# Tiny_BLE_V1_0.net
KiCad netlist of a schematic drawn in EAGLE
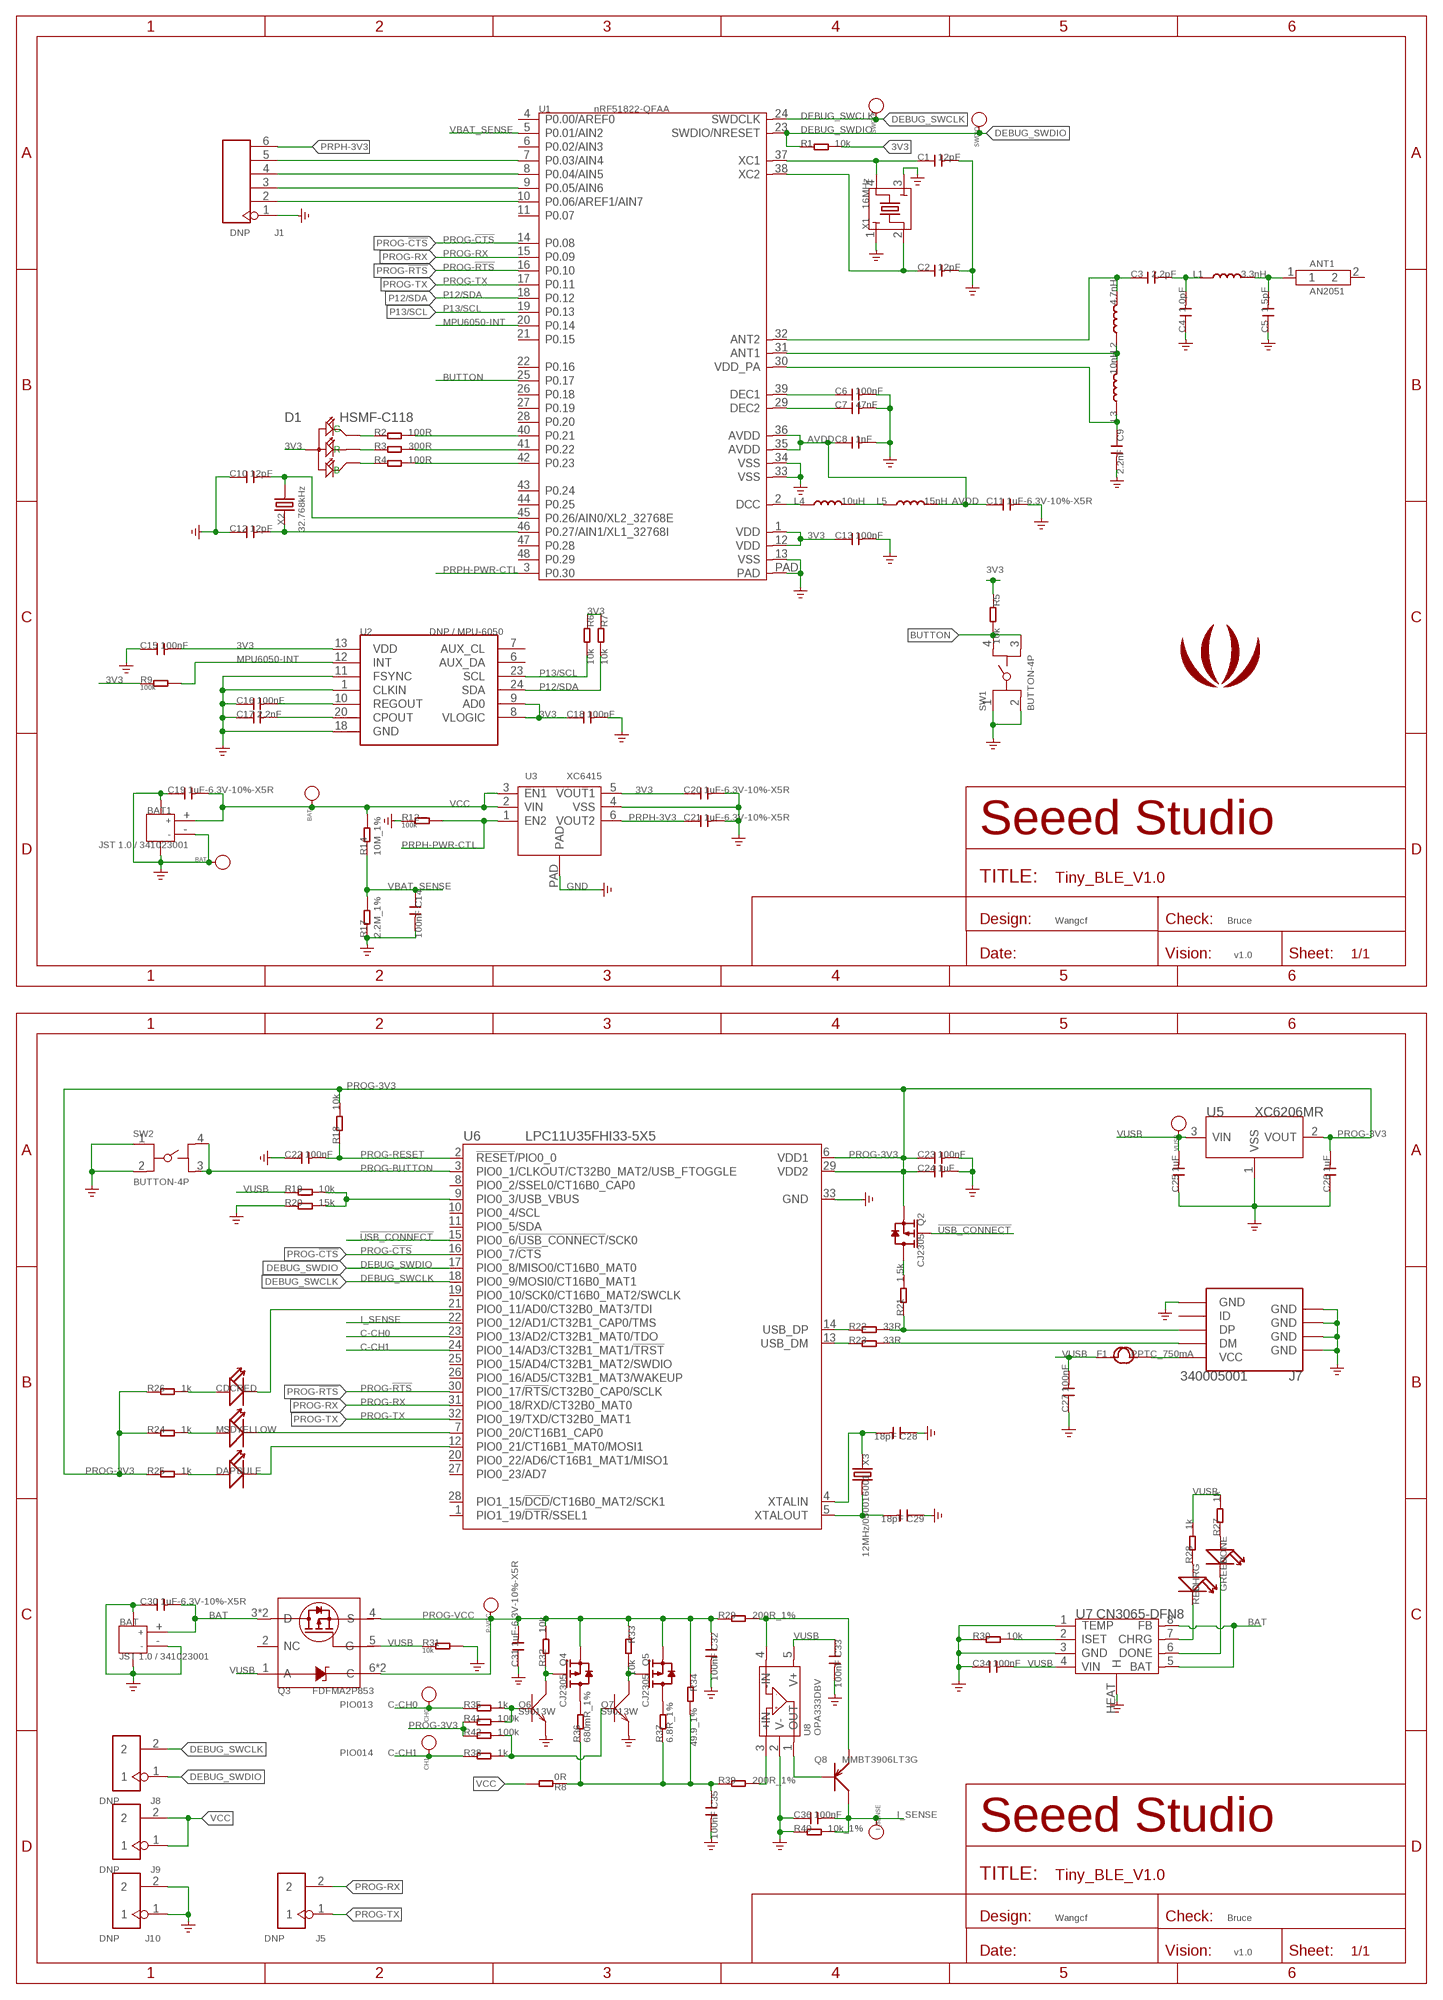
[diagram p0: schematic, sheet 1]

(export (version "E")
  (design (tool "Eeschema 10.0.6"))
  (components
    (comp (ref "ANT1")
      (value "AN2051")
      (footprint "eagle-import:2P-SMD-L5.05_W.02_H1.07MM")
      (libsource (lib "eagle-import") (part "ANTENNA-2.4GHZ-0.5DBI'AN2051'"))
    )
    (comp (ref "BAT")
      (value "JST 1.0 / 341023001")
      (footprint "eagle-import:JST-SMD-2P-1.0-90D")
      (libsource (lib "eagle-import") (part "JACK-JST-2P-SMD-PW'1.0'"))
    )
    (comp (ref "BAT+")
      (value "BAT+")
      (footprint "eagle-import:PAD_4080")
      (libsource (lib "eagle-import") (part "PAD-TEST-POINT'4080'"))
    )
    (comp (ref "BAT-")
      (value "BAT-")
      (footprint "eagle-import:PAD_4080")
      (libsource (lib "eagle-import") (part "PAD-TEST-POINT'4080'"))
    )
    (comp (ref "BAT1")
      (value "JST 1.0 / 341023001")
      (footprint "eagle-import:JST-SMD-2P-1.0-90D")
      (libsource (lib "eagle-import") (part "JACK-JST-2P-SMD-PW'1.0'"))
    )
    (comp (ref "C1")
      (value "12pF")
      (footprint "eagle-import:C0402")
      (libsource (lib "eagle-import") (part "C-0402"))
    )
    (comp (ref "C2")
      (value "12pF")
      (footprint "eagle-import:C0402")
      (libsource (lib "eagle-import") (part "C-0402"))
    )
    (comp (ref "C3")
      (value "2.2pF")
      (footprint "eagle-import:C0402")
      (libsource (lib "eagle-import") (part "C-0402"))
    )
    (comp (ref "C4")
      (value "1.0pF")
      (footprint "eagle-import:C0402")
      (libsource (lib "eagle-import") (part "C-0402"))
    )
    (comp (ref "C5")
      (value "1.5pF")
      (footprint "eagle-import:C0402")
      (libsource (lib "eagle-import") (part "C-0402"))
    )
    (comp (ref "C6")
      (value "100nF")
      (footprint "eagle-import:C0402")
      (libsource (lib "eagle-import") (part "C-0402"))
    )
    (comp (ref "C7")
      (value "47nF")
      (footprint "eagle-import:C0402")
      (libsource (lib "eagle-import") (part "C-0402"))
    )
    (comp (ref "C8")
      (value "1nF")
      (footprint "eagle-import:C0402")
      (libsource (lib "eagle-import") (part "C-0402"))
    )
    (comp (ref "C9")
      (value "2.2nF")
      (footprint "eagle-import:C0402")
      (libsource (lib "eagle-import") (part "C-0402"))
    )
    (comp (ref "C10")
      (value "12pF")
      (footprint "eagle-import:C0402")
      (libsource (lib "eagle-import") (part "C-0402"))
    )
    (comp (ref "C11")
      (value "1uF-6.3V-10%-X5R")
      (footprint "eagle-import:C0402")
      (libsource (lib "eagle-import") (part "C-0402"))
    )
    (comp (ref "C12")
      (value "12pF")
      (footprint "eagle-import:C0402")
      (libsource (lib "eagle-import") (part "C-0402"))
    )
    (comp (ref "C13")
      (value "100nF")
      (footprint "eagle-import:C0402")
      (libsource (lib "eagle-import") (part "C-0402"))
    )
    (comp (ref "C14")
      (value "100nF")
      (footprint "eagle-import:C0402")
      (libsource (lib "eagle-import") (part "C-0402"))
    )
    (comp (ref "C15")
      (value "100nF")
      (footprint "eagle-import:C0402")
      (libsource (lib "eagle-import") (part "C-0402"))
    )
    (comp (ref "C16")
      (value "100nF")
      (footprint "eagle-import:C0402")
      (libsource (lib "eagle-import") (part "C-0402"))
    )
    (comp (ref "C17")
      (value "2.2nF")
      (footprint "eagle-import:C0402")
      (libsource (lib "eagle-import") (part "C-0402"))
    )
    (comp (ref "C18")
      (value "100nF")
      (footprint "eagle-import:C0402")
      (libsource (lib "eagle-import") (part "C-0402"))
    )
    (comp (ref "C19")
      (value "1uF-6.3V-10%-X5R")
      (footprint "eagle-import:C0402")
      (libsource (lib "eagle-import") (part "C-0402"))
    )
    (comp (ref "C20")
      (value "1uF-6.3V-10%-X5R")
      (footprint "eagle-import:C0402")
      (libsource (lib "eagle-import") (part "C-0402"))
    )
    (comp (ref "C21")
      (value "1uF-6.3V-10%-X5R")
      (footprint "eagle-import:C0402")
      (libsource (lib "eagle-import") (part "C-0402"))
    )
    (comp (ref "C22")
      (value "100nF")
      (footprint "eagle-import:C0402")
      (libsource (lib "eagle-import") (part "C-0402"))
    )
    (comp (ref "C23")
      (value "100nF")
      (footprint "eagle-import:C0402")
      (libsource (lib "eagle-import") (part "C-0402"))
    )
    (comp (ref "C24")
      (value "1uF")
      (footprint "eagle-import:C0402")
      (libsource (lib "eagle-import") (part "C-0402"))
    )
    (comp (ref "C25")
      (value "1uF")
      (footprint "eagle-import:C0402")
      (libsource (lib "eagle-import") (part "C-0402"))
    )
    (comp (ref "C26")
      (value "1uF")
      (footprint "eagle-import:C0402")
      (libsource (lib "eagle-import") (part "C-0402"))
    )
    (comp (ref "C27")
      (value "100nF")
      (footprint "eagle-import:C0402")
      (libsource (lib "eagle-import") (part "C-0402"))
    )
    (comp (ref "C28")
      (value "18pF")
      (footprint "eagle-import:C0402")
      (libsource (lib "eagle-import") (part "C-0402"))
    )
    (comp (ref "C29")
      (value "18pF")
      (footprint "eagle-import:C0402")
      (libsource (lib "eagle-import") (part "C-0402"))
    )
    (comp (ref "C30")
      (value "1uF-6.3V-10%-X5R")
      (footprint "eagle-import:C0402")
      (libsource (lib "eagle-import") (part "C-0402"))
    )
    (comp (ref "C31")
      (value "1uF-6.3V-10%-X5R")
      (footprint "eagle-import:C0402")
      (libsource (lib "eagle-import") (part "C-0402"))
    )
    (comp (ref "C32")
      (value "100nF")
      (footprint "eagle-import:C0402")
      (libsource (lib "eagle-import") (part "C-0402"))
    )
    (comp (ref "C33")
      (value "100nF")
      (footprint "eagle-import:C0402")
      (libsource (lib "eagle-import") (part "C-0402"))
    )
    (comp (ref "C34")
      (value "100nF")
      (footprint "eagle-import:C0402")
      (libsource (lib "eagle-import") (part "C-0402"))
    )
    (comp (ref "C35")
      (value "100nF")
      (footprint "eagle-import:C0402")
      (libsource (lib "eagle-import") (part "C-0402"))
    )
    (comp (ref "C36")
      (value "100nF")
      (footprint "eagle-import:C0402")
      (libsource (lib "eagle-import") (part "C-0402"))
    )
    (comp (ref "CDC")
      (value "RED")
      (footprint "eagle-import:LED-0603")
      (libsource (lib "eagle-import") (part "LED'0603'"))
    )
    (comp (ref "CH0")
      (value "CH0")
      (footprint "eagle-import:TP_4545")
      (fields (field (name "PARTNO") "DNP"))
      (libsource (lib "eagle-import") (part "PAD-TEST-POINT'4545'"))
    )
    (comp (ref "CH1")
      (value "CH1")
      (footprint "eagle-import:TP_4545")
      (fields (field (name "PARTNO") "DNP"))
      (libsource (lib "eagle-import") (part "PAD-TEST-POINT'4545'"))
    )
    (comp (ref "CHRG")
      (value "RED")
      (footprint "eagle-import:LED-0603")
      (libsource (lib "eagle-import") (part "LED'0603'"))
    )
    (comp (ref "D1")
      (value "HSMF-C118")
      (footprint "eagle-import:LED-4P-1210-3.0X2.54")
      (libsource (lib "eagle-import") (part "LED-ARGB-4P-1210"))
    )
    (comp (ref "DAP")
      (value "BULE")
      (footprint "eagle-import:LED-0603")
      (libsource (lib "eagle-import") (part "LED'0603'"))
    )
    (comp (ref "DONE")
      (value "GREEN")
      (footprint "eagle-import:LED-0603")
      (libsource (lib "eagle-import") (part "LED'0603'"))
    )
    (comp (ref "F1")
      (value "PPTC_750mA")
      (footprint "eagle-import:F1206")
      (libsource (lib "eagle-import") (part "FUSE'1206'"))
    )
    (comp (ref "I_SENSE")
      (value "I_SENSE")
      (footprint "eagle-import:TP_4545")
      (fields (field (name "PARTNO") "DNP"))
      (libsource (lib "eagle-import") (part "PAD-TEST-POINT'4545'"))
    )
    (comp (ref "J1")
      (value "DNP")
      (footprint "eagle-import:6P-2.54-60_35MIL")
      (libsource (lib "eagle-import") (part "HEADER-6P-60/35MIL"))
    )
    (comp (ref "J5")
      (value "DNP")
      (footprint "eagle-import:2P-2.54-65_35MIL")
      (libsource (lib "eagle-import") (part "HEADER-2P-65/35MIL"))
    )
    (comp (ref "J7")
      (value "340005001")
      (footprint "eagle-import:MICRO-USB")
      (libsource (lib "eagle-import") (part "USB-MINIUSB-5P-MICRO"))
    )
    (comp (ref "J8")
      (value "DNP")
      (footprint "eagle-import:2P-2.54-65_35MIL")
      (libsource (lib "eagle-import") (part "HEADER-2P-65/35MIL"))
    )
    (comp (ref "J9")
      (value "DNP")
      (footprint "eagle-import:2P-2.54-65_35MIL")
      (libsource (lib "eagle-import") (part "HEADER-2P-65/35MIL"))
    )
    (comp (ref "J10")
      (value "DNP")
      (footprint "eagle-import:2P-2.54-65_35MIL")
      (libsource (lib "eagle-import") (part "HEADER-2P-65/35MIL"))
    )
    (comp (ref "L1")
      (value "3.3nH")
      (footprint "eagle-import:L0402")
      (libsource (lib "eagle-import") (part "L'0402'"))
    )
    (comp (ref "L2")
      (value "4.7nH")
      (footprint "eagle-import:L0402")
      (libsource (lib "eagle-import") (part "L'0402'"))
    )
    (comp (ref "L3")
      (value "10nH")
      (footprint "eagle-import:L0402")
      (libsource (lib "eagle-import") (part "L'0402'"))
    )
    (comp (ref "L4")
      (value "10uH")
      (footprint "eagle-import:L0603")
      (libsource (lib "eagle-import") (part "L'0603'"))
    )
    (comp (ref "L5")
      (value "15nH")
      (footprint "eagle-import:L0402")
      (libsource (lib "eagle-import") (part "L'0402'"))
    )
    (comp (ref "MSD")
      (value "YELLOW")
      (footprint "eagle-import:LED-0603")
      (libsource (lib "eagle-import") (part "LED'0603'"))
    )
    (comp (ref "P-VCC")
      (value "P_VCC")
      (footprint "eagle-import:TP_4545")
      (fields (field (name "PARTNO") "DNP"))
      (libsource (lib "eagle-import") (part "PAD-TEST-POINT'4545'"))
    )
    (comp (ref "Q2")
      (value "CJ2305")
      (footprint "eagle-import:SOT23")
      (libsource (lib "eagle-import") (part "MOSFET-P'SI2323CDS/SI2305DS{lt}BR{gt}'"))
    )
    (comp (ref "Q3")
      (value "FDFMA2P853")
      (footprint "eagle-import:6P-SMD-W_-HEAT")
      (libsource (lib "eagle-import") (part "FDFMA2P853"))
    )
    (comp (ref "Q4")
      (value "CJ2305")
      (footprint "eagle-import:SOT23")
      (libsource (lib "eagle-import") (part "MOSFET-P'SI2323CDS/SI2305DS{lt}BR{gt}'"))
    )
    (comp (ref "Q5")
      (value "CJ2305")
      (footprint "eagle-import:SOT23")
      (libsource (lib "eagle-import") (part "MOSFET-P'SI2323CDS/SI2305DS{lt}BR{gt}'"))
    )
    (comp (ref "Q6")
      (value "S9013W")
      (footprint "eagle-import:SOT323")
      (libsource (lib "eagle-import") (part "TRANSISTOR-NPN-SOT323"))
    )
    (comp (ref "Q7")
      (value "S9013W")
      (footprint "eagle-import:SOT323")
      (libsource (lib "eagle-import") (part "TRANSISTOR-NPN-SOT323"))
    )
    (comp (ref "Q8")
      (value "MMBT3906LT3G")
      (footprint "eagle-import:SOT23")
      (libsource (lib "eagle-import") (part "TRANSISTOR-PNP-SOT23"))
    )
    (comp (ref "R1")
      (value "10k")
      (footprint "eagle-import:R0402")
      (libsource (lib "eagle-import") (part "R-0402"))
    )
    (comp (ref "R2")
      (value "100R")
      (footprint "eagle-import:R0402")
      (libsource (lib "eagle-import") (part "R-0402"))
    )
    (comp (ref "R3")
      (value "300R")
      (footprint "eagle-import:R0402")
      (libsource (lib "eagle-import") (part "R-0402"))
    )
    (comp (ref "R4")
      (value "100R")
      (footprint "eagle-import:R0402")
      (libsource (lib "eagle-import") (part "R-0402"))
    )
    (comp (ref "R5")
      (value "10k")
      (footprint "eagle-import:R0402")
      (libsource (lib "eagle-import") (part "R-0402"))
    )
    (comp (ref "R6")
      (value "10k")
      (footprint "eagle-import:R0402")
      (libsource (lib "eagle-import") (part "R-0402"))
    )
    (comp (ref "R7")
      (value "10k")
      (footprint "eagle-import:R0402")
      (libsource (lib "eagle-import") (part "R-0402"))
    )
    (comp (ref "R8")
      (value "0R")
      (footprint "eagle-import:R0603")
      (libsource (lib "eagle-import") (part "R-0603"))
    )
    (comp (ref "R9")
      (value "100k")
      (footprint "eagle-import:R0402")
      (libsource (lib "eagle-import") (part "R-0402"))
    )
    (comp (ref "R12")
      (value "100k")
      (footprint "eagle-import:R0402")
      (libsource (lib "eagle-import") (part "R-0402"))
    )
    (comp (ref "R14")
      (value "10M_1%")
      (footprint "eagle-import:R0402")
      (libsource (lib "eagle-import") (part "R-0402"))
    )
    (comp (ref "R17")
      (value "2.2M_1%")
      (footprint "eagle-import:R0402")
      (libsource (lib "eagle-import") (part "R-0402"))
    )
    (comp (ref "R18")
      (value "10k")
      (footprint "eagle-import:R0402")
      (libsource (lib "eagle-import") (part "R-0402"))
    )
    (comp (ref "R19")
      (value "10k")
      (footprint "eagle-import:R0402")
      (libsource (lib "eagle-import") (part "R-0402"))
    )
    (comp (ref "R20")
      (value "15k")
      (footprint "eagle-import:R0402")
      (libsource (lib "eagle-import") (part "R-0402"))
    )
    (comp (ref "R21")
      (value "1.5k")
      (footprint "eagle-import:R0402")
      (libsource (lib "eagle-import") (part "R-0402"))
    )
    (comp (ref "R22")
      (value "33R")
      (footprint "eagle-import:R0402")
      (libsource (lib "eagle-import") (part "R-0402"))
    )
    (comp (ref "R23")
      (value "33R")
      (footprint "eagle-import:R0402")
      (libsource (lib "eagle-import") (part "R-0402"))
    )
    (comp (ref "R24")
      (value "1k")
      (footprint "eagle-import:R0402")
      (libsource (lib "eagle-import") (part "R-0402"))
    )
    (comp (ref "R25")
      (value "1k")
      (footprint "eagle-import:R0402")
      (libsource (lib "eagle-import") (part "R-0402"))
    )
    (comp (ref "R26")
      (value "1k")
      (footprint "eagle-import:R0402")
      (libsource (lib "eagle-import") (part "R-0402"))
    )
    (comp (ref "R27")
      (value "1k")
      (footprint "eagle-import:R0402")
      (libsource (lib "eagle-import") (part "R-0402"))
    )
    (comp (ref "R28")
      (value "1k")
      (footprint "eagle-import:R0402")
      (libsource (lib "eagle-import") (part "R-0402"))
    )
    (comp (ref "R29")
      (value "200R_1%")
      (footprint "eagle-import:R0402")
      (libsource (lib "eagle-import") (part "R-0402"))
    )
    (comp (ref "R30")
      (value "10k")
      (footprint "eagle-import:R0402")
      (libsource (lib "eagle-import") (part "R-0402"))
    )
    (comp (ref "R31")
      (value "10k")
      (footprint "eagle-import:R0402")
      (libsource (lib "eagle-import") (part "R-0402"))
    )
    (comp (ref "R32")
      (value "10k")
      (footprint "eagle-import:R0402")
      (libsource (lib "eagle-import") (part "R-0402"))
    )
    (comp (ref "R33")
      (value "10k")
      (footprint "eagle-import:R0402")
      (libsource (lib "eagle-import") (part "R-0402"))
    )
    (comp (ref "R34")
      (value "49.9_1%")
      (footprint "eagle-import:R0603")
      (libsource (lib "eagle-import") (part "R-0603"))
    )
    (comp (ref "R35")
      (value "1k")
      (footprint "eagle-import:R0402")
      (libsource (lib "eagle-import") (part "R-0402"))
    )
    (comp (ref "R36")
      (value "680mR_1%")
      (footprint "eagle-import:R0603")
      (libsource (lib "eagle-import") (part "R-0603"))
    )
    (comp (ref "R37")
      (value "6.8R_1%")
      (footprint "eagle-import:R0603")
      (libsource (lib "eagle-import") (part "R-0603"))
    )
    (comp (ref "R38")
      (value "1k")
      (footprint "eagle-import:R0402")
      (libsource (lib "eagle-import") (part "R-0402"))
    )
    (comp (ref "R39")
      (value "200R_1%")
      (footprint "eagle-import:R0402")
      (libsource (lib "eagle-import") (part "R-0402"))
    )
    (comp (ref "R40")
      (value "10k_1%")
      (footprint "eagle-import:R0402")
      (libsource (lib "eagle-import") (part "R-0402"))
    )
    (comp (ref "R41")
      (value "100k")
      (footprint "eagle-import:R0402")
      (libsource (lib "eagle-import") (part "R-0402"))
    )
    (comp (ref "R42")
      (value "100k")
      (footprint "eagle-import:R0402")
      (libsource (lib "eagle-import") (part "R-0402"))
    )
    (comp (ref "SW1")
      (value "BUTTON-4P")
      (footprint "eagle-import:4P-SMD-L4.45_W3.22_H2.5MM")
      (libsource (lib "eagle-import") (part "BUTTON-4P"))
    )
    (comp (ref "SW2")
      (value "BUTTON-4P")
      (footprint "eagle-import:4P-SMD-L4.45_W3.22_H2.5MM")
      (libsource (lib "eagle-import") (part "BUTTON-4P"))
    )
    (comp (ref "SWCLK")
      (value "SWDCLK")
      (footprint "eagle-import:PAD_4080")
      (libsource (lib "eagle-import") (part "PAD-TEST-POINT'4080'"))
    )
    (comp (ref "SWDIO")
      (value "SWDIO")
      (footprint "eagle-import:PAD_4080")
      (libsource (lib "eagle-import") (part "PAD-TEST-POINT'4080'"))
    )
    (comp (ref "U$59")
      (value "LOGO-SEEEDSTUDIO-SMALL-SILK")
      (footprint "eagle-import:SMALL_SEEED_LOGO")
      (fields (field (name "PARTNO") "DNP"))
      (libsource (lib "eagle-import") (part "LOGO-SEEEDSTUDIO-SMALL-SILK"))
    )
    (comp (ref "U1")
      (value "nRF51822-QFAA")
      (footprint "eagle-import:QFN48-6X6MM")
      (libsource (lib "eagle-import") (part "NRF51822"))
    )
    (comp (ref "U2")
      (value "DNP / MPU-6050")
      (footprint "eagle-import:QFN24")
      (libsource (lib "eagle-import") (part "MPU-6050‘’"))
    )
    (comp (ref "U3")
      (value "XC6415")
      (footprint "eagle-import:USP-6C")
      (libsource (lib "eagle-import") (part "XC6415"))
    )
    (comp (ref "U5")
      (value "XC6206MR")
      (footprint "eagle-import:SOT23")
      (libsource (lib "eagle-import") (part "XC6206MR"))
    )
    (comp (ref "U6")
      (value "LPC11U35FHI33-5X5")
      (footprint "eagle-import:HVQFN33")
      (libsource (lib "eagle-import") (part "LPC11U35FHI33-5X5"))
    )
    (comp (ref "U7")
      (value "CN3065-DFN8")
      (footprint "eagle-import:DFN8")
      (libsource (lib "eagle-import") (part "CN3065-DFN8"))
    )
    (comp (ref "U8")
      (value "OPA333DBV")
      (footprint "eagle-import:SOT23-5")
      (libsource (lib "eagle-import") (part "OPA333DBV"))
    )
    (comp (ref "VUSB")
      (value "VUSB")
      (footprint "eagle-import:TP_4545")
      (fields (field (name "PARTNO") "DNP"))
      (libsource (lib "eagle-import") (part "PAD-TEST-POINT'4545'"))
    )
    (comp (ref "X1")
      (value "16MHz")
      (footprint "eagle-import:2520")
      (libsource (lib "eagle-import") (part "CRYSTAL'-2520'"))
    )
    (comp (ref "X2")
      (value "32.768kHz")
      (footprint "eagle-import:2P-SMD-3.2X1.5")
      (libsource (lib "eagle-import") (part "CRYSTAL-3215"))
    )
    (comp (ref "X3")
      (value "12MHz/050016001")
      (footprint "eagle-import:2P-SMD-5X3.2")
      (libsource (lib "eagle-import") (part "CRYSTAL'5032'"))
    )
  )
  (nets
    (net (code "1") (name "/AVDD") (class "Default")
      (node (ref "C11") (pin "1") (pinfunction "1_1") (pintype "passive"))
      (node (ref "C8") (pin "1") (pinfunction "1_1") (pintype "passive"))
      (node (ref "L5") (pin "2") (pinfunction "2_2") (pintype "passive"))
      (node (ref "U1") (pin "35") (pinfunction "AVDD_35") (pintype "bidirectional"))
      (node (ref "U1") (pin "36") (pinfunction "AVDD_36") (pintype "bidirectional"))
    )
    (net (code "2") (name "/BAT") (class "Default")
      (node (ref "BAT") (pin "+") (pinfunction "1_+") (pintype "bidirectional"))
      (node (ref "C30") (pin "2") (pinfunction "2_2") (pintype "passive"))
      (node (ref "Q3") (pin "3") (pinfunction "D_3") (pintype "bidirectional"))
      (node (ref "Q3") (pin "P2") (pinfunction "D_P2") (pintype "bidirectional"))
      (node (ref "U7") (pin "5") (pinfunction "BAT_5") (pintype "bidirectional"))
      (node (ref "U7") (pin "8") (pinfunction "FB_8") (pintype "input"))
    )
    (net (code "3") (name "/C-CH0") (class "Default")
      (node (ref "CH0") (pin "T") (pinfunction "T_T") (pintype "bidirectional"))
      (node (ref "R35") (pin "1") (pinfunction "1_1") (pintype "passive"))
      (node (ref "U6") (pin "23") (pinfunction "PIO0_13/AD2/CT32B1_MAT0/TDO_23") (pintype "bidirectional"))
    )
    (net (code "4") (name "/C-CH1") (class "Default")
      (node (ref "CH1") (pin "T") (pinfunction "T_T") (pintype "bidirectional"))
      (node (ref "R38") (pin "1") (pinfunction "1_1") (pintype "passive"))
      (node (ref "U6") (pin "24") (pinfunction "PIO0_14/AD3/CT32B1_MAT1/~{TRST}_24") (pintype "bidirectional"))
    )
    (net (code "5") (name "/I_SENSE") (class "Default")
      (node (ref "C36") (pin "2") (pinfunction "2_2") (pintype "passive"))
      (node (ref "I_SENSE") (pin "T") (pinfunction "T_T") (pintype "bidirectional"))
      (node (ref "Q8") (pin "3") (pinfunction "C_3") (pintype "passive"))
      (node (ref "R40") (pin "2") (pinfunction "2_2") (pintype "passive"))
      (node (ref "U6") (pin "22") (pinfunction "PIO0_12/AD1/CT32B1_CAP0/TMS_22") (pintype "bidirectional"))
    )
    (net (code "6") (name "/MPU6050-INT") (class "Default")
      (node (ref "R9") (pin "2") (pinfunction "2_2") (pintype "passive"))
      (node (ref "U1") (pin "20") (pinfunction "P0.14_20") (pintype "bidirectional"))
      (node (ref "U2") (pin "12") (pinfunction "INT_12") (pintype "bidirectional"))
    )
    (net (code "7") (name "/PROG-3V3") (class "Default")
      (node (ref "C23") (pin "1") (pinfunction "1_1") (pintype "passive"))
      (node (ref "C24") (pin "1") (pinfunction "1_1") (pintype "passive"))
      (node (ref "C26") (pin "2") (pinfunction "2_2") (pintype "passive"))
      (node (ref "Q2") (pin "2") (pinfunction "S_2") (pintype "passive"))
      (node (ref "R18") (pin "2") (pinfunction "2_2") (pintype "passive"))
      (node (ref "R24") (pin "1") (pinfunction "1_1") (pintype "passive"))
      (node (ref "R25") (pin "1") (pinfunction "1_1") (pintype "passive"))
      (node (ref "R26") (pin "1") (pinfunction "1_1") (pintype "passive"))
      (node (ref "R41") (pin "1") (pinfunction "1_1") (pintype "passive"))
      (node (ref "R42") (pin "1") (pinfunction "1_1") (pintype "passive"))
      (node (ref "U5") (pin "2") (pinfunction "VOUT_2") (pintype "output"))
      (node (ref "U6") (pin "29") (pinfunction "VDD2_29") (pintype "bidirectional"))
      (node (ref "U6") (pin "6") (pinfunction "VDD1_6") (pintype "bidirectional"))
    )
    (net (code "8") (name "/PROG-BUTTON") (class "Default")
      (node (ref "SW2") (pin "3") (pinfunction "3_3") (pintype "bidirectional"))
      (node (ref "SW2") (pin "4") (pinfunction "4_4") (pintype "bidirectional"))
      (node (ref "U6") (pin "3") (pinfunction "PIO0_1/CLKOUT/CT32B0_MAT2/USB_FTOGGLE_3") (pintype "bidirectional"))
    )
    (net (code "9") (name "/PROG-RESET") (class "Default")
      (node (ref "C22") (pin "2") (pinfunction "2_2") (pintype "passive"))
      (node (ref "R18") (pin "1") (pinfunction "1_1") (pintype "passive"))
      (node (ref "U6") (pin "2") (pinfunction "~{RESET}/PIO0_0_2") (pintype "bidirectional"))
    )
    (net (code "10") (name "/PROG-VCC") (class "Default")
      (node (ref "C31") (pin "2") (pinfunction "2_2") (pintype "passive"))
      (node (ref "C32") (pin "1") (pinfunction "1_1") (pintype "passive"))
      (node (ref "P-VCC") (pin "T") (pinfunction "T_T") (pintype "bidirectional"))
      (node (ref "Q3") (pin "4") (pinfunction "S_4") (pintype "bidirectional"))
      (node (ref "Q3") (pin "6") (pinfunction "C_6") (pintype "bidirectional"))
      (node (ref "Q3") (pin "P1") (pinfunction "C_P1") (pintype "bidirectional"))
      (node (ref "Q4") (pin "2") (pinfunction "S_2") (pintype "passive"))
      (node (ref "Q5") (pin "2") (pinfunction "S_2") (pintype "passive"))
      (node (ref "R29") (pin "1") (pinfunction "1_1") (pintype "passive"))
      (node (ref "R32") (pin "2") (pinfunction "2_2") (pintype "passive"))
      (node (ref "R33") (pin "1") (pinfunction "1_1") (pintype "passive"))
      (node (ref "R34") (pin "1") (pinfunction "1_1") (pintype "passive"))
    )
    (net (code "11") (name "/PROG-~{CTS}") (class "Default")
      (node (ref "U1") (pin "14") (pinfunction "P0.08_14") (pintype "bidirectional"))
      (node (ref "U6") (pin "16") (pinfunction "PIO0_7/~{CTS}_16") (pintype "bidirectional"))
    )
    (net (code "12") (name "/PROG-~{RTS}") (class "Default")
      (node (ref "U1") (pin "16") (pinfunction "P0.10_16") (pintype "bidirectional"))
      (node (ref "U6") (pin "30") (pinfunction "PIO0_17/~{RTS}/CT32B0_CAP0/SCLK_30") (pintype "bidirectional"))
    )
    (net (code "13") (name "/PRPH-PWR-CTL") (class "Default")
      (node (ref "R12") (pin "2") (pinfunction "2_2") (pintype "passive"))
      (node (ref "U1") (pin "3") (pinfunction "P0.30_3") (pintype "bidirectional"))
      (node (ref "U3") (pin "1") (pinfunction "EN2_1") (pintype "bidirectional"))
    )
    (net (code "14") (name "/VBAT_SENSE") (class "Default")
      (node (ref "C14") (pin "1") (pinfunction "1_1") (pintype "passive"))
      (node (ref "R14") (pin "1") (pinfunction "1_1") (pintype "passive"))
      (node (ref "R17") (pin "2") (pinfunction "2_2") (pintype "passive"))
      (node (ref "U1") (pin "5") (pinfunction "P0.01/AIN2_5") (pintype "bidirectional"))
    )
    (net (code "15") (name "/VUSB") (class "Default")
      (node (ref "C25") (pin "2") (pinfunction "2_2") (pintype "passive"))
      (node (ref "C27") (pin "2") (pinfunction "2_2") (pintype "passive"))
      (node (ref "C33") (pin "1") (pinfunction "1_1") (pintype "passive"))
      (node (ref "C34") (pin "2") (pinfunction "2_2") (pintype "passive"))
      (node (ref "F1") (pin "1") (pinfunction "1_1") (pintype "bidirectional"))
      (node (ref "Q3") (pin "1") (pinfunction "A_1") (pintype "bidirectional"))
      (node (ref "Q3") (pin "5") (pinfunction "G_5") (pintype "bidirectional"))
      (node (ref "R19") (pin "1") (pinfunction "1_1") (pintype "passive"))
      (node (ref "R27") (pin "2") (pinfunction "2_2") (pintype "passive"))
      (node (ref "R28") (pin "2") (pinfunction "2_2") (pintype "passive"))
      (node (ref "R31") (pin "1") (pinfunction "1_1") (pintype "passive"))
      (node (ref "U5") (pin "3") (pinfunction "VIN_3") (pintype "input"))
      (node (ref "U7") (pin "4") (pinfunction "VIN_4") (pintype "input"))
      (node (ref "U8") (pin "5") (pinfunction "V+_5") (pintype "bidirectional"))
      (node (ref "VUSB") (pin "T") (pinfunction "T_T") (pintype "bidirectional"))
    )
    (net (code "16") (name "/~{USB_CONNECT}") (class "Default")
      (node (ref "Q2") (pin "1") (pinfunction "G_1") (pintype "passive"))
      (node (ref "U6") (pin "15") (pinfunction "PIO0_6/~{USB_CONNECT}/SCK0_15") (pintype "bidirectional"))
    )
    (net (code "17") (name "3V3") (class "Default")
      (node (ref "C13") (pin "1") (pinfunction "1_1") (pintype "passive"))
      (node (ref "C15") (pin "2") (pinfunction "2_2") (pintype "passive"))
      (node (ref "C18") (pin "1") (pinfunction "1_1") (pintype "passive"))
      (node (ref "C20") (pin "1") (pinfunction "1_1") (pintype "passive"))
      (node (ref "D1") (pin "1") (pinfunction "+_1") (pintype "bidirectional"))
      (node (ref "R1") (pin "2") (pinfunction "2_2") (pintype "passive"))
      (node (ref "R5") (pin "1") (pinfunction "1_1") (pintype "passive"))
      (node (ref "R6") (pin "1") (pinfunction "1_1") (pintype "passive"))
      (node (ref "R7") (pin "1") (pinfunction "1_1") (pintype "passive"))
      (node (ref "R9") (pin "1") (pinfunction "1_1") (pintype "passive"))
      (node (ref "U1") (pin "1") (pinfunction "VDD_1") (pintype "bidirectional"))
      (node (ref "U1") (pin "12") (pinfunction "VDD_12") (pintype "bidirectional"))
      (node (ref "U2") (pin "13") (pinfunction "VDD_13") (pintype "bidirectional"))
      (node (ref "U2") (pin "8") (pinfunction "VLOGIC_8") (pintype "bidirectional"))
      (node (ref "U2") (pin "9") (pinfunction "AD0_9") (pintype "bidirectional"))
      (node (ref "U3") (pin "5") (pinfunction "VOUT1_5") (pintype "bidirectional"))
    )
    (net (code "18") (name "BUTTON") (class "Default")
      (node (ref "R5") (pin "2") (pinfunction "2_2") (pintype "passive"))
      (node (ref "SW1") (pin "3") (pinfunction "3_3") (pintype "bidirectional"))
      (node (ref "SW1") (pin "4") (pinfunction "4_4") (pintype "bidirectional"))
      (node (ref "U1") (pin "25") (pinfunction "P0.17_25") (pintype "bidirectional"))
    )
    (net (code "19") (name "DEBUG_SWCLK") (class "Default")
      (node (ref "J8") (pin "2") (pinfunction "2_2") (pintype "bidirectional"))
      (node (ref "SWCLK") (pin "1") (pinfunction "T_1") (pintype "bidirectional"))
      (node (ref "U1") (pin "24") (pinfunction "SWDCLK_24") (pintype "bidirectional"))
      (node (ref "U6") (pin "18") (pinfunction "PIO0_9/MOSI0/CT16B0_MAT1_18") (pintype "bidirectional"))
    )
    (net (code "20") (name "DEBUG_SWDIO") (class "Default")
      (node (ref "J8") (pin "1") (pinfunction "1_1") (pintype "bidirectional"))
      (node (ref "R1") (pin "1") (pinfunction "1_1") (pintype "passive"))
      (node (ref "SWDIO") (pin "1") (pinfunction "T_1") (pintype "bidirectional"))
      (node (ref "U1") (pin "23") (pinfunction "SWDIO/NRESET_23") (pintype "bidirectional"))
      (node (ref "U6") (pin "17") (pinfunction "PIO0_8/MISO0/CT16B0_MAT0_17") (pintype "bidirectional"))
    )
    (net (code "21") (name "GND_POWER") (class "Default")
      (node (ref "BAT") (pin "-") (pinfunction "2_-") (pintype "bidirectional"))
      (node (ref "BAT") (pin "3") (pinfunction "3_3") (pintype "bidirectional"))
      (node (ref "BAT") (pin "4") (pinfunction "4_4") (pintype "bidirectional"))
      (node (ref "BAT-") (pin "1") (pinfunction "T_1") (pintype "bidirectional"))
      (node (ref "BAT1") (pin "-") (pinfunction "2_-") (pintype "bidirectional"))
      (node (ref "BAT1") (pin "3") (pinfunction "3_3") (pintype "bidirectional"))
      (node (ref "BAT1") (pin "4") (pinfunction "4_4") (pintype "bidirectional"))
      (node (ref "C1") (pin "2") (pinfunction "2_2") (pintype "passive"))
      (node (ref "C10") (pin "1") (pinfunction "1_1") (pintype "passive"))
      (node (ref "C11") (pin "2") (pinfunction "2_2") (pintype "passive"))
      (node (ref "C12") (pin "1") (pinfunction "1_1") (pintype "passive"))
      (node (ref "C13") (pin "2") (pinfunction "2_2") (pintype "passive"))
      (node (ref "C14") (pin "2") (pinfunction "2_2") (pintype "passive"))
      (node (ref "C15") (pin "1") (pinfunction "1_1") (pintype "passive"))
      (node (ref "C16") (pin "1") (pinfunction "1_1") (pintype "passive"))
      (node (ref "C17") (pin "1") (pinfunction "1_1") (pintype "passive"))
      (node (ref "C18") (pin "2") (pinfunction "2_2") (pintype "passive"))
      (node (ref "C19") (pin "1") (pinfunction "1_1") (pintype "passive"))
      (node (ref "C2") (pin "2") (pinfunction "2_2") (pintype "passive"))
      (node (ref "C20") (pin "2") (pinfunction "2_2") (pintype "passive"))
      (node (ref "C21") (pin "2") (pinfunction "2_2") (pintype "passive"))
      (node (ref "C22") (pin "1") (pinfunction "1_1") (pintype "passive"))
      (node (ref "C23") (pin "2") (pinfunction "2_2") (pintype "passive"))
      (node (ref "C24") (pin "2") (pinfunction "2_2") (pintype "passive"))
      (node (ref "C25") (pin "1") (pinfunction "1_1") (pintype "passive"))
      (node (ref "C26") (pin "1") (pinfunction "1_1") (pintype "passive"))
      (node (ref "C27") (pin "1") (pinfunction "1_1") (pintype "passive"))
      (node (ref "C28") (pin "1") (pinfunction "1_1") (pintype "passive"))
      (node (ref "C29") (pin "1") (pinfunction "1_1") (pintype "passive"))
      (node (ref "C30") (pin "1") (pinfunction "1_1") (pintype "passive"))
      (node (ref "C31") (pin "1") (pinfunction "1_1") (pintype "passive"))
      (node (ref "C32") (pin "2") (pinfunction "2_2") (pintype "passive"))
      (node (ref "C33") (pin "2") (pinfunction "2_2") (pintype "passive"))
      (node (ref "C34") (pin "1") (pinfunction "1_1") (pintype "passive"))
      (node (ref "C35") (pin "2") (pinfunction "2_2") (pintype "passive"))
      (node (ref "C36") (pin "1") (pinfunction "1_1") (pintype "passive"))
      (node (ref "C4") (pin "1") (pinfunction "1_1") (pintype "passive"))
      (node (ref "C5") (pin "1") (pinfunction "1_1") (pintype "passive"))
      (node (ref "C6") (pin "2") (pinfunction "2_2") (pintype "passive"))
      (node (ref "C7") (pin "2") (pinfunction "2_2") (pintype "passive"))
      (node (ref "C8") (pin "2") (pinfunction "2_2") (pintype "passive"))
      (node (ref "C9") (pin "2") (pinfunction "2_2") (pintype "passive"))
      (node (ref "J1") (pin "1") (pinfunction "1_1") (pintype "bidirectional"))
      (node (ref "J10") (pin "1") (pinfunction "1_1") (pintype "bidirectional"))
      (node (ref "J10") (pin "2") (pinfunction "2_2") (pintype "bidirectional"))
      (node (ref "J7") (pin "5") (pinfunction "GND_5") (pintype "bidirectional"))
      (node (ref "J7") (pin "S1") (pinfunction "GND_S1") (pintype "bidirectional"))
      (node (ref "J7") (pin "S2") (pinfunction "GND_S2") (pintype "bidirectional"))
      (node (ref "J7") (pin "S3") (pinfunction "GND_S3") (pintype "bidirectional"))
      (node (ref "J7") (pin "S4") (pinfunction "GND_S4") (pintype "bidirectional"))
      (node (ref "J7") (pin "S5") (pinfunction "GND_S5") (pintype "bidirectional"))
      (node (ref "J7") (pin "S6") (pinfunction "GND_S6") (pintype "bidirectional"))
      (node (ref "Q6") (pin "2") (pinfunction "E_2") (pintype "passive"))
      (node (ref "Q7") (pin "2") (pinfunction "E_2") (pintype "passive"))
      (node (ref "R12") (pin "1") (pinfunction "1_1") (pintype "passive"))
      (node (ref "R17") (pin "1") (pinfunction "1_1") (pintype "passive"))
      (node (ref "R20") (pin "1") (pinfunction "1_1") (pintype "passive"))
      (node (ref "R30") (pin "1") (pinfunction "1_1") (pintype "passive"))
      (node (ref "R31") (pin "2") (pinfunction "2_2") (pintype "passive"))
      (node (ref "R40") (pin "1") (pinfunction "1_1") (pintype "passive"))
      (node (ref "SW1") (pin "1") (pinfunction "1_1") (pintype "bidirectional"))
      (node (ref "SW1") (pin "2") (pinfunction "2_2") (pintype "bidirectional"))
      (node (ref "SW2") (pin "1") (pinfunction "1_1") (pintype "bidirectional"))
      (node (ref "SW2") (pin "2") (pinfunction "2_2") (pintype "bidirectional"))
      (node (ref "U1") (pin "13") (pinfunction "VSS_13") (pintype "bidirectional"))
      (node (ref "U1") (pin "33") (pinfunction "VSS_33") (pintype "bidirectional"))
      (node (ref "U1") (pin "34") (pinfunction "VSS_34") (pintype "bidirectional"))
      (node (ref "U1") (pin "PAD") (pinfunction "PAD_PAD") (pintype "bidirectional"))
      (node (ref "U2") (pin "1") (pinfunction "CLKIN_1") (pintype "bidirectional"))
      (node (ref "U2") (pin "11") (pinfunction "FSYNC_11") (pintype "bidirectional"))
      (node (ref "U2") (pin "18") (pinfunction "GND_18") (pintype "bidirectional"))
      (node (ref "U3") (pin "4") (pinfunction "VSS_4") (pintype "bidirectional"))
      (node (ref "U3") (pin "PAD") (pinfunction "PAD_PAD") (pintype "bidirectional"))
      (node (ref "U5") (pin "1") (pinfunction "VSS_1") (pintype "power_in"))
      (node (ref "U6") (pin "33") (pinfunction "GND_33") (pintype "bidirectional"))
      (node (ref "U7") (pin "1") (pinfunction "TEMP_1") (pintype "input"))
      (node (ref "U7") (pin "3") (pinfunction "GND_3") (pintype "power_in"))
      (node (ref "U7") (pin "HEAT") (pinfunction "H_HEAT") (pintype "bidirectional"))
      (node (ref "U8") (pin "2") (pinfunction "V-_2") (pintype "bidirectional"))
      (node (ref "X1") (pin "1") (pinfunction "1_1") (pintype "bidirectional"))
      (node (ref "X1") (pin "3") (pinfunction "3_3") (pintype "bidirectional"))
    )
    (net (code "22") (name "Net-(ANT1-Pad1)") (class "Default")
      (node (ref "ANT1") (pin "1") (pinfunction "1_1") (pintype "bidirectional"))
      (node (ref "C5") (pin "2") (pinfunction "2_2") (pintype "passive"))
      (node (ref "L1") (pin "2") (pinfunction "2_2") (pintype "passive"))
    )
    (net (code "23") (name "Net-(C3-Pad2)") (class "Default")
      (node (ref "C3") (pin "2") (pinfunction "2_2") (pintype "passive"))
      (node (ref "C4") (pin "2") (pinfunction "2_2") (pintype "passive"))
      (node (ref "L1") (pin "1") (pinfunction "1_1") (pintype "passive"))
    )
    (net (code "24") (name "Net-(C35-Pad1)") (class "Default")
      (node (ref "C35") (pin "1") (pinfunction "1_1") (pintype "passive"))
      (node (ref "R34") (pin "2") (pinfunction "2_2") (pintype "passive"))
      (node (ref "R36") (pin "1") (pinfunction "1_1") (pintype "passive"))
      (node (ref "R37") (pin "1") (pinfunction "1_1") (pintype "passive"))
      (node (ref "R39") (pin "1") (pinfunction "1_1") (pintype "passive"))
      (node (ref "R8") (pin "1") (pinfunction "1_1") (pintype "passive"))
    )
    (net (code "25") (name "Net-(CDC-Pad+)") (class "Default")
      (node (ref "CDC") (pin "+") (pinfunction "+_+") (pintype "passive"))
      (node (ref "R26") (pin "2") (pinfunction "2_2") (pintype "passive"))
    )
    (net (code "26") (name "Net-(CHRG-Pad+)") (class "Default")
      (node (ref "CHRG") (pin "+") (pinfunction "+_+") (pintype "passive"))
      (node (ref "R28") (pin "1") (pinfunction "1_1") (pintype "passive"))
    )
    (net (code "27") (name "Net-(D1-B)") (class "Default")
      (node (ref "D1") (pin "4") (pinfunction "B_4") (pintype "bidirectional"))
      (node (ref "R4") (pin "1") (pinfunction "1_1") (pintype "passive"))
    )
    (net (code "28") (name "Net-(D1-G)") (class "Default")
      (node (ref "D1") (pin "3") (pinfunction "G_3") (pintype "bidirectional"))
      (node (ref "R2") (pin "1") (pinfunction "1_1") (pintype "passive"))
    )
    (net (code "29") (name "Net-(D1-R)") (class "Default")
      (node (ref "D1") (pin "2") (pinfunction "R_2") (pintype "bidirectional"))
      (node (ref "R3") (pin "1") (pinfunction "1_1") (pintype "passive"))
    )
    (net (code "30") (name "Net-(DAP-Pad+)") (class "Default")
      (node (ref "DAP") (pin "+") (pinfunction "+_+") (pintype "passive"))
      (node (ref "R25") (pin "2") (pinfunction "2_2") (pintype "passive"))
    )
    (net (code "31") (name "Net-(DONE-Pad+)") (class "Default")
      (node (ref "DONE") (pin "+") (pinfunction "+_+") (pintype "passive"))
      (node (ref "R27") (pin "1") (pinfunction "1_1") (pintype "passive"))
    )
    (net (code "32") (name "Net-(J7-DM)") (class "Default")
      (node (ref "J7") (pin "2") (pinfunction "DM_2") (pintype "bidirectional"))
      (node (ref "R23") (pin "2") (pinfunction "2_2") (pintype "passive"))
    )
    (net (code "33") (name "Net-(J7-DP)") (class "Default")
      (node (ref "J7") (pin "3") (pinfunction "DP_3") (pintype "bidirectional"))
      (node (ref "R21") (pin "1") (pinfunction "1_1") (pintype "passive"))
      (node (ref "R22") (pin "2") (pinfunction "2_2") (pintype "passive"))
    )
    (net (code "34") (name "Net-(J7-VCC)") (class "Default")
      (node (ref "F1") (pin "2") (pinfunction "2_2") (pintype "bidirectional"))
      (node (ref "J7") (pin "1") (pinfunction "VCC_1") (pintype "bidirectional"))
    )
    (net (code "35") (name "Net-(L4-Pad2)") (class "Default")
      (node (ref "L4") (pin "2") (pinfunction "2_2") (pintype "passive"))
      (node (ref "L5") (pin "1") (pinfunction "1_1") (pintype "passive"))
    )
    (net (code "36") (name "Net-(MSD-Pad+)") (class "Default")
      (node (ref "MSD") (pin "+") (pinfunction "+_+") (pintype "passive"))
      (node (ref "R24") (pin "2") (pinfunction "2_2") (pintype "passive"))
    )
    (net (code "37") (name "Net-(Q2-D)") (class "Default")
      (node (ref "Q2") (pin "3") (pinfunction "D_3") (pintype "passive"))
      (node (ref "R21") (pin "2") (pinfunction "2_2") (pintype "passive"))
    )
    (net (code "38") (name "Net-(Q4-D)") (class "Default")
      (node (ref "Q4") (pin "3") (pinfunction "D_3") (pintype "passive"))
      (node (ref "R36") (pin "2") (pinfunction "2_2") (pintype "passive"))
    )
    (net (code "39") (name "Net-(Q4-G)") (class "Default")
      (node (ref "Q4") (pin "1") (pinfunction "G_1") (pintype "passive"))
      (node (ref "Q6") (pin "3") (pinfunction "C_3") (pintype "passive"))
      (node (ref "R32") (pin "1") (pinfunction "1_1") (pintype "passive"))
    )
    (net (code "40") (name "Net-(Q5-D)") (class "Default")
      (node (ref "Q5") (pin "3") (pinfunction "D_3") (pintype "passive"))
      (node (ref "R37") (pin "2") (pinfunction "2_2") (pintype "passive"))
    )
    (net (code "41") (name "Net-(Q5-G)") (class "Default")
      (node (ref "Q5") (pin "1") (pinfunction "G_1") (pintype "passive"))
      (node (ref "Q7") (pin "3") (pinfunction "C_3") (pintype "passive"))
      (node (ref "R33") (pin "2") (pinfunction "2_2") (pintype "passive"))
    )
    (net (code "42") (name "Net-(Q6-B)") (class "Default")
      (node (ref "Q6") (pin "1") (pinfunction "B_1") (pintype "passive"))
      (node (ref "R35") (pin "2") (pinfunction "2_2") (pintype "passive"))
      (node (ref "R41") (pin "2") (pinfunction "2_2") (pintype "passive"))
    )
    (net (code "43") (name "Net-(Q7-B)") (class "Default")
      (node (ref "Q7") (pin "1") (pinfunction "B_1") (pintype "passive"))
      (node (ref "R38") (pin "2") (pinfunction "2_2") (pintype "passive"))
      (node (ref "R42") (pin "2") (pinfunction "2_2") (pintype "passive"))
    )
    (net (code "44") (name "Net-(Q8-B)") (class "Default")
      (node (ref "Q8") (pin "1") (pinfunction "B_1") (pintype "passive"))
      (node (ref "U8") (pin "1") (pinfunction "OUT_1") (pintype "bidirectional"))
    )
    (net (code "45") (name "Net-(Q8-E)") (class "Default")
      (node (ref "Q8") (pin "2") (pinfunction "E_2") (pintype "passive"))
      (node (ref "R29") (pin "2") (pinfunction "2_2") (pintype "passive"))
      (node (ref "U8") (pin "4") (pinfunction "-IN_4") (pintype "bidirectional"))
    )
    (net (code "46") (name "Net-(U1-ANT1)") (class "Default")
      (node (ref "L2") (pin "1") (pinfunction "1_1") (pintype "passive"))
      (node (ref "L3") (pin "2") (pinfunction "2_2") (pintype "passive"))
      (node (ref "U1") (pin "31") (pinfunction "ANT1_31") (pintype "bidirectional"))
    )
    (net (code "47") (name "Net-(U1-ANT2)") (class "Default")
      (node (ref "C3") (pin "1") (pinfunction "1_1") (pintype "passive"))
      (node (ref "L2") (pin "2") (pinfunction "2_2") (pintype "passive"))
      (node (ref "U1") (pin "32") (pinfunction "ANT2_32") (pintype "bidirectional"))
    )
    (net (code "48") (name "Net-(U1-DCC)") (class "Default")
      (node (ref "L4") (pin "1") (pinfunction "1_1") (pintype "passive"))
      (node (ref "U1") (pin "2") (pinfunction "DCC_2") (pintype "bidirectional"))
    )
    (net (code "49") (name "Net-(U1-DEC1)") (class "Default")
      (node (ref "C6") (pin "1") (pinfunction "1_1") (pintype "passive"))
      (node (ref "U1") (pin "39") (pinfunction "DEC1_39") (pintype "bidirectional"))
    )
    (net (code "50") (name "Net-(U1-DEC2)") (class "Default")
      (node (ref "C7") (pin "1") (pinfunction "1_1") (pintype "passive"))
      (node (ref "U1") (pin "29") (pinfunction "DEC2_29") (pintype "bidirectional"))
    )
    (net (code "51") (name "Net-(U1-P0.03{slash}AIN4)") (class "Default")
      (node (ref "J1") (pin "5") (pinfunction "5_5") (pintype "bidirectional"))
      (node (ref "U1") (pin "7") (pinfunction "P0.03/AIN4_7") (pintype "bidirectional"))
    )
    (net (code "52") (name "Net-(U1-P0.04{slash}AIN5)") (class "Default")
      (node (ref "J1") (pin "4") (pinfunction "4_4") (pintype "bidirectional"))
      (node (ref "U1") (pin "8") (pinfunction "P0.04/AIN5_8") (pintype "bidirectional"))
    )
    (net (code "53") (name "Net-(U1-P0.05{slash}AIN6)") (class "Default")
      (node (ref "J1") (pin "3") (pinfunction "3_3") (pintype "bidirectional"))
      (node (ref "U1") (pin "9") (pinfunction "P0.05/AIN6_9") (pintype "bidirectional"))
    )
    (net (code "54") (name "Net-(U1-P0.06{slash}AREF1{slash}AIN7)") (class "Default")
      (node (ref "J1") (pin "2") (pinfunction "2_2") (pintype "bidirectional"))
      (node (ref "U1") (pin "10") (pinfunction "P0.06/AREF1/AIN7_10") (pintype "bidirectional"))
    )
    (net (code "55") (name "Net-(U1-P0.21)") (class "Default")
      (node (ref "R2") (pin "2") (pinfunction "2_2") (pintype "passive"))
      (node (ref "U1") (pin "40") (pinfunction "P0.21_40") (pintype "bidirectional"))
    )
    (net (code "56") (name "Net-(U1-P0.22)") (class "Default")
      (node (ref "R3") (pin "2") (pinfunction "2_2") (pintype "passive"))
      (node (ref "U1") (pin "41") (pinfunction "P0.22_41") (pintype "bidirectional"))
    )
    (net (code "57") (name "Net-(U1-P0.23)") (class "Default")
      (node (ref "R4") (pin "2") (pinfunction "2_2") (pintype "passive"))
      (node (ref "U1") (pin "42") (pinfunction "P0.23_42") (pintype "bidirectional"))
    )
    (net (code "58") (name "Net-(U1-P0.26{slash}AIN0{slash}XL2_32768E)") (class "Default")
      (node (ref "C10") (pin "2") (pinfunction "2_2") (pintype "passive"))
      (node (ref "U1") (pin "45") (pinfunction "P0.26/AIN0/XL2_32768E_45") (pintype "bidirectional"))
      (node (ref "X2") (pin "2") (pinfunction "2_2") (pintype "passive"))
    )
    (net (code "59") (name "Net-(U1-P0.27{slash}AIN1{slash}XL1_32768I)") (class "Default")
      (node (ref "C12") (pin "2") (pinfunction "2_2") (pintype "passive"))
      (node (ref "U1") (pin "46") (pinfunction "P0.27/AIN1/XL1_32768I_46") (pintype "bidirectional"))
      (node (ref "X2") (pin "1") (pinfunction "1_1") (pintype "passive"))
    )
    (net (code "60") (name "Net-(U1-VDD_PA)") (class "Default")
      (node (ref "C9") (pin "1") (pinfunction "1_1") (pintype "passive"))
      (node (ref "L3") (pin "1") (pinfunction "1_1") (pintype "passive"))
      (node (ref "U1") (pin "30") (pinfunction "VDD_PA_30") (pintype "bidirectional"))
    )
    (net (code "61") (name "Net-(U1-XC1)") (class "Default")
      (node (ref "C1") (pin "1") (pinfunction "1_1") (pintype "passive"))
      (node (ref "U1") (pin "37") (pinfunction "XC1_37") (pintype "bidirectional"))
      (node (ref "X1") (pin "4") (pinfunction "4_4") (pintype "passive"))
    )
    (net (code "62") (name "Net-(U1-XC2)") (class "Default")
      (node (ref "C2") (pin "1") (pinfunction "1_1") (pintype "passive"))
      (node (ref "U1") (pin "38") (pinfunction "XC2_38") (pintype "bidirectional"))
      (node (ref "X1") (pin "2") (pinfunction "2_2") (pintype "passive"))
    )
    (net (code "63") (name "Net-(U2-CPOUT)") (class "Default")
      (node (ref "C17") (pin "2") (pinfunction "2_2") (pintype "passive"))
      (node (ref "U2") (pin "20") (pinfunction "CPOUT_20") (pintype "bidirectional"))
    )
    (net (code "64") (name "Net-(U2-REGOUT)") (class "Default")
      (node (ref "C16") (pin "2") (pinfunction "2_2") (pintype "passive"))
      (node (ref "U2") (pin "10") (pinfunction "REGOUT_10") (pintype "bidirectional"))
    )
    (net (code "65") (name "Net-(U6-PIO0_3{slash}USB_VBUS)") (class "Default")
      (node (ref "R19") (pin "2") (pinfunction "2_2") (pintype "passive"))
      (node (ref "R20") (pin "2") (pinfunction "2_2") (pintype "passive"))
      (node (ref "U6") (pin "9") (pinfunction "PIO0_3/USB_VBUS_9") (pintype "bidirectional"))
    )
    (net (code "66") (name "Net-(U6-PIO0_11{slash}AD0{slash}CT32B0_MAT3{slash}TDI)") (class "Default")
      (node (ref "CDC") (pin "-") (pinfunction "-_-") (pintype "passive"))
      (node (ref "U6") (pin "21") (pinfunction "PIO0_11/AD0/CT32B0_MAT3/TDI_21") (pintype "bidirectional"))
    )
    (net (code "67") (name "Net-(U6-PIO0_20{slash}CT16B1_CAP0)") (class "Default")
      (node (ref "MSD") (pin "-") (pinfunction "-_-") (pintype "passive"))
      (node (ref "U6") (pin "7") (pinfunction "PIO0_20/CT16B1_CAP0_7") (pintype "bidirectional"))
    )
    (net (code "68") (name "Net-(U6-PIO0_21{slash}CT16B1_MAT0{slash}MOSI1)") (class "Default")
      (node (ref "DAP") (pin "-") (pinfunction "-_-") (pintype "passive"))
      (node (ref "U6") (pin "12") (pinfunction "PIO0_21/CT16B1_MAT0/MOSI1_12") (pintype "bidirectional"))
    )
    (net (code "69") (name "Net-(U6-USB_DM)") (class "Default")
      (node (ref "R23") (pin "1") (pinfunction "1_1") (pintype "passive"))
      (node (ref "U6") (pin "13") (pinfunction "USB_DM_13") (pintype "bidirectional"))
    )
    (net (code "70") (name "Net-(U6-USB_DP)") (class "Default")
      (node (ref "R22") (pin "1") (pinfunction "1_1") (pintype "passive"))
      (node (ref "U6") (pin "14") (pinfunction "USB_DP_14") (pintype "bidirectional"))
    )
    (net (code "71") (name "Net-(U6-XTALIN)") (class "Default")
      (node (ref "C28") (pin "2") (pinfunction "2_2") (pintype "passive"))
      (node (ref "U6") (pin "4") (pinfunction "XTALIN_4") (pintype "bidirectional"))
      (node (ref "X3") (pin "1") (pinfunction "1_1") (pintype "passive"))
    )
    (net (code "72") (name "Net-(U6-XTALOUT)") (class "Default")
      (node (ref "C29") (pin "2") (pinfunction "2_2") (pintype "passive"))
      (node (ref "U6") (pin "5") (pinfunction "XTALOUT_5") (pintype "bidirectional"))
      (node (ref "X3") (pin "2") (pinfunction "2_2") (pintype "passive"))
    )
    (net (code "73") (name "Net-(U7-CHRG)") (class "Default")
      (node (ref "CHRG") (pin "-") (pinfunction "-_-") (pintype "passive"))
      (node (ref "U7") (pin "7") (pinfunction "CHRG_7") (pintype "bidirectional"))
    )
    (net (code "74") (name "Net-(U7-DONE)") (class "Default")
      (node (ref "DONE") (pin "-") (pinfunction "-_-") (pintype "passive"))
      (node (ref "U7") (pin "6") (pinfunction "DONE_6") (pintype "bidirectional"))
    )
    (net (code "75") (name "Net-(U7-ISET)") (class "Default")
      (node (ref "R30") (pin "2") (pinfunction "2_2") (pintype "passive"))
      (node (ref "U7") (pin "2") (pinfunction "ISET_2") (pintype "bidirectional"))
    )
    (net (code "76") (name "Net-(U8-+IN)") (class "Default")
      (node (ref "R39") (pin "2") (pinfunction "2_2") (pintype "passive"))
      (node (ref "U8") (pin "3") (pinfunction "+IN_3") (pintype "bidirectional"))
    )
    (net (code "77") (name "P12{slash}SDA") (class "Default")
      (node (ref "R7") (pin "2") (pinfunction "2_2") (pintype "passive"))
      (node (ref "U1") (pin "18") (pinfunction "P0.12_18") (pintype "bidirectional"))
      (node (ref "U2") (pin "24") (pinfunction "SDA_24") (pintype "bidirectional"))
    )
    (net (code "78") (name "P13{slash}SCL") (class "Default")
      (node (ref "R6") (pin "2") (pinfunction "2_2") (pintype "passive"))
      (node (ref "U1") (pin "19") (pinfunction "P0.13_19") (pintype "bidirectional"))
      (node (ref "U2") (pin "23") (pinfunction "SCL_23") (pintype "bidirectional"))
    )
    (net (code "79") (name "PROG-RX") (class "Default")
      (node (ref "J5") (pin "2") (pinfunction "2_2") (pintype "bidirectional"))
      (node (ref "U1") (pin "15") (pinfunction "P0.09_15") (pintype "bidirectional"))
      (node (ref "U6") (pin "31") (pinfunction "PIO0_18/RXD/CT32B0_MAT0_31") (pintype "bidirectional"))
    )
    (net (code "80") (name "PROG-TX") (class "Default")
      (node (ref "J5") (pin "1") (pinfunction "1_1") (pintype "bidirectional"))
      (node (ref "U1") (pin "17") (pinfunction "P0.11_17") (pintype "bidirectional"))
      (node (ref "U6") (pin "32") (pinfunction "PIO0_19/TXD/CT32B0_MAT1_32") (pintype "bidirectional"))
    )
    (net (code "81") (name "PRPH-3V3") (class "Default")
      (node (ref "C21") (pin "1") (pinfunction "1_1") (pintype "passive"))
      (node (ref "J1") (pin "6") (pinfunction "6_6") (pintype "bidirectional"))
      (node (ref "U3") (pin "6") (pinfunction "VOUT2_6") (pintype "bidirectional"))
    )
    (net (code "82") (name "VCC") (class "Default")
      (node (ref "BAT+") (pin "1") (pinfunction "T_1") (pintype "bidirectional"))
      (node (ref "BAT1") (pin "+") (pinfunction "1_+") (pintype "bidirectional"))
      (node (ref "C19") (pin "2") (pinfunction "2_2") (pintype "passive"))
      (node (ref "J9") (pin "1") (pinfunction "1_1") (pintype "bidirectional"))
      (node (ref "J9") (pin "2") (pinfunction "2_2") (pintype "bidirectional"))
      (node (ref "R14") (pin "2") (pinfunction "2_2") (pintype "passive"))
      (node (ref "R8") (pin "2") (pinfunction "2_2") (pintype "passive"))
      (node (ref "U3") (pin "2") (pinfunction "VIN_2") (pintype "bidirectional"))
      (node (ref "U3") (pin "3") (pinfunction "EN1_3") (pintype "bidirectional"))
    )
    (net (code "83") (name "unconnected-(ANT1-Pad2)") (class "Default")
      (node (ref "ANT1") (pin "2") (pinfunction "2_2") (pintype "bidirectional"))
    )
    (net (code "84") (name "unconnected-(J7-ID-Pad4)") (class "Default")
      (node (ref "J7") (pin "4") (pinfunction "ID_4") (pintype "bidirectional"))
    )
    (net (code "85") (name "unconnected-(Q3-NC-Pad2)") (class "Default")
      (node (ref "Q3") (pin "2") (pinfunction "NC_2") (pintype "bidirectional"))
    )
    (net (code "86") (name "unconnected-(U1-P0.00{slash}AREF0-Pad4)") (class "Default")
      (node (ref "U1") (pin "4") (pinfunction "P0.00/AREF0_4") (pintype "bidirectional"))
    )
    (net (code "87") (name "unconnected-(U1-P0.02{slash}AIN3-Pad6)") (class "Default")
      (node (ref "U1") (pin "6") (pinfunction "P0.02/AIN3_6") (pintype "bidirectional"))
    )
    (net (code "88") (name "unconnected-(U1-P0.07-Pad11)") (class "Default")
      (node (ref "U1") (pin "11") (pinfunction "P0.07_11") (pintype "bidirectional"))
    )
    (net (code "89") (name "unconnected-(U1-P0.15-Pad21)") (class "Default")
      (node (ref "U1") (pin "21") (pinfunction "P0.15_21") (pintype "bidirectional"))
    )
    (net (code "90") (name "unconnected-(U1-P0.16-Pad22)") (class "Default")
      (node (ref "U1") (pin "22") (pinfunction "P0.16_22") (pintype "bidirectional"))
    )
    (net (code "91") (name "unconnected-(U1-P0.18-Pad26)") (class "Default")
      (node (ref "U1") (pin "26") (pinfunction "P0.18_26") (pintype "bidirectional"))
    )
    (net (code "92") (name "unconnected-(U1-P0.19-Pad27)") (class "Default")
      (node (ref "U1") (pin "27") (pinfunction "P0.19_27") (pintype "bidirectional"))
    )
    (net (code "93") (name "unconnected-(U1-P0.20-Pad28)") (class "Default")
      (node (ref "U1") (pin "28") (pinfunction "P0.20_28") (pintype "bidirectional"))
    )
    (net (code "94") (name "unconnected-(U1-P0.24-Pad43)") (class "Default")
      (node (ref "U1") (pin "43") (pinfunction "P0.24_43") (pintype "bidirectional"))
    )
    (net (code "95") (name "unconnected-(U1-P0.25-Pad44)") (class "Default")
      (node (ref "U1") (pin "44") (pinfunction "P0.25_44") (pintype "bidirectional"))
    )
    (net (code "96") (name "unconnected-(U1-P0.28-Pad47)") (class "Default")
      (node (ref "U1") (pin "47") (pinfunction "P0.28_47") (pintype "bidirectional"))
    )
    (net (code "97") (name "unconnected-(U1-P0.29-Pad48)") (class "Default")
      (node (ref "U1") (pin "48") (pinfunction "P0.29_48") (pintype "bidirectional"))
    )
    (net (code "98") (name "unconnected-(U2-AUX_CL-Pad7)") (class "Default")
      (node (ref "U2") (pin "7") (pinfunction "AUX_CL_7") (pintype "bidirectional"))
    )
    (net (code "99") (name "unconnected-(U2-AUX_DA-Pad6)") (class "Default")
      (node (ref "U2") (pin "6") (pinfunction "AUX_DA_6") (pintype "bidirectional"))
    )
    (net (code "100") (name "unconnected-(U6-PIO0_2{slash}SSEL0{slash}CT16B0_CAP0-Pad8)") (class "Default")
      (node (ref "U6") (pin "8") (pinfunction "PIO0_2/SSEL0/CT16B0_CAP0_8") (pintype "bidirectional"))
    )
    (net (code "101") (name "unconnected-(U6-PIO0_4{slash}SCL-Pad10)") (class "Default")
      (node (ref "U6") (pin "10") (pinfunction "PIO0_4/SCL_10") (pintype "bidirectional"))
    )
    (net (code "102") (name "unconnected-(U6-PIO0_5{slash}SDA-Pad11)") (class "Default")
      (node (ref "U6") (pin "11") (pinfunction "PIO0_5/SDA_11") (pintype "bidirectional"))
    )
    (net (code "103") (name "unconnected-(U6-PIO0_10{slash}SCK0{slash}CT16B0_MAT2{slash}SWCLK-Pad19)") (class "Default")
      (node (ref "U6") (pin "19") (pinfunction "PIO0_10/SCK0/CT16B0_MAT2/SWCLK_19") (pintype "bidirectional"))
    )
    (net (code "104") (name "unconnected-(U6-PIO0_15{slash}AD4{slash}CT32B1_MAT2{slash}SWDIO-Pad25)") (class "Default")
      (node (ref "U6") (pin "25") (pinfunction "PIO0_15/AD4/CT32B1_MAT2/SWDIO_25") (pintype "bidirectional"))
    )
    (net (code "105") (name "unconnected-(U6-PIO0_16{slash}AD5{slash}CT32B1_MAT3{slash}WAKEUP-Pad26)") (class "Default")
      (node (ref "U6") (pin "26") (pinfunction "PIO0_16/AD5/CT32B1_MAT3/WAKEUP_26") (pintype "bidirectional"))
    )
    (net (code "106") (name "unconnected-(U6-PIO0_22{slash}AD6{slash}CT16B1_MAT1{slash}MISO1-Pad20)") (class "Default")
      (node (ref "U6") (pin "20") (pinfunction "PIO0_22/AD6/CT16B1_MAT1/MISO1_20") (pintype "bidirectional"))
    )
    (net (code "107") (name "unconnected-(U6-PIO0_23{slash}AD7-Pad27)") (class "Default")
      (node (ref "U6") (pin "27") (pinfunction "PIO0_23/AD7_27") (pintype "bidirectional"))
    )
    (net (code "108") (name "unconnected-(U6-PIO1_15{slash}~{DCD}{slash}CT16B0_MAT2{slash}SCK1-Pad28)") (class "Default")
      (node (ref "U6") (pin "28") (pinfunction "PIO1_15/~{DCD}/CT16B0_MAT2/SCK1_28") (pintype "bidirectional"))
    )
    (net (code "109") (name "unconnected-(U6-PIO1_19{slash}~{DTR}{slash}SSEL1-Pad1)") (class "Default")
      (node (ref "U6") (pin "1") (pinfunction "PIO1_19/~{DTR}/SSEL1_1") (pintype "bidirectional"))
    )
  )
)
